# Wilssen_core_v0_201a.net
KiCad netlist of a schematic drawn in EAGLE
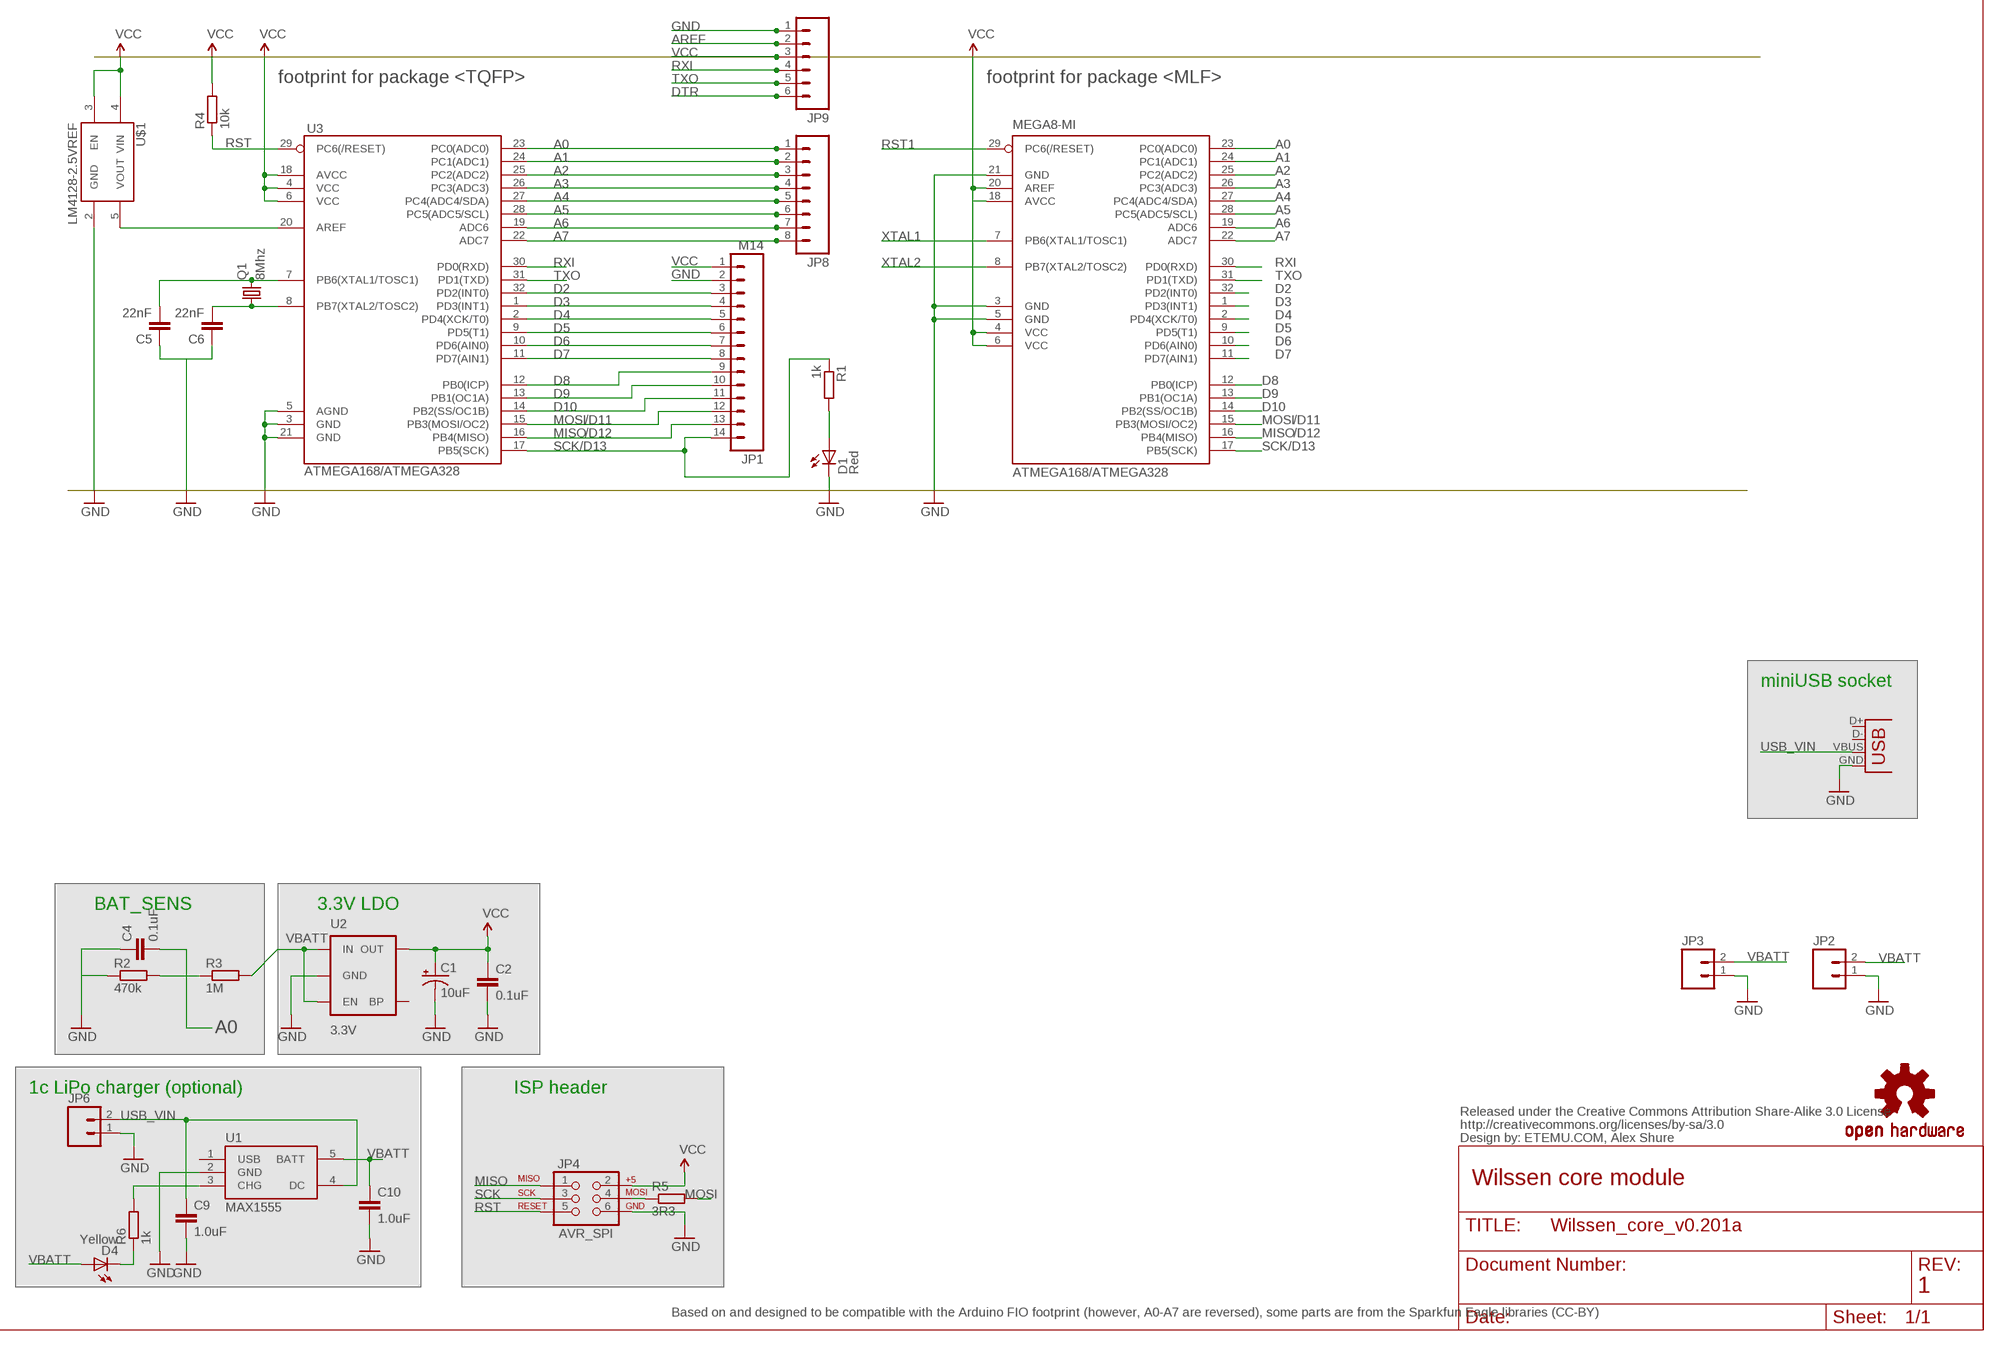
[diagram p0: schematic, sheet 1, part 1 of 2]
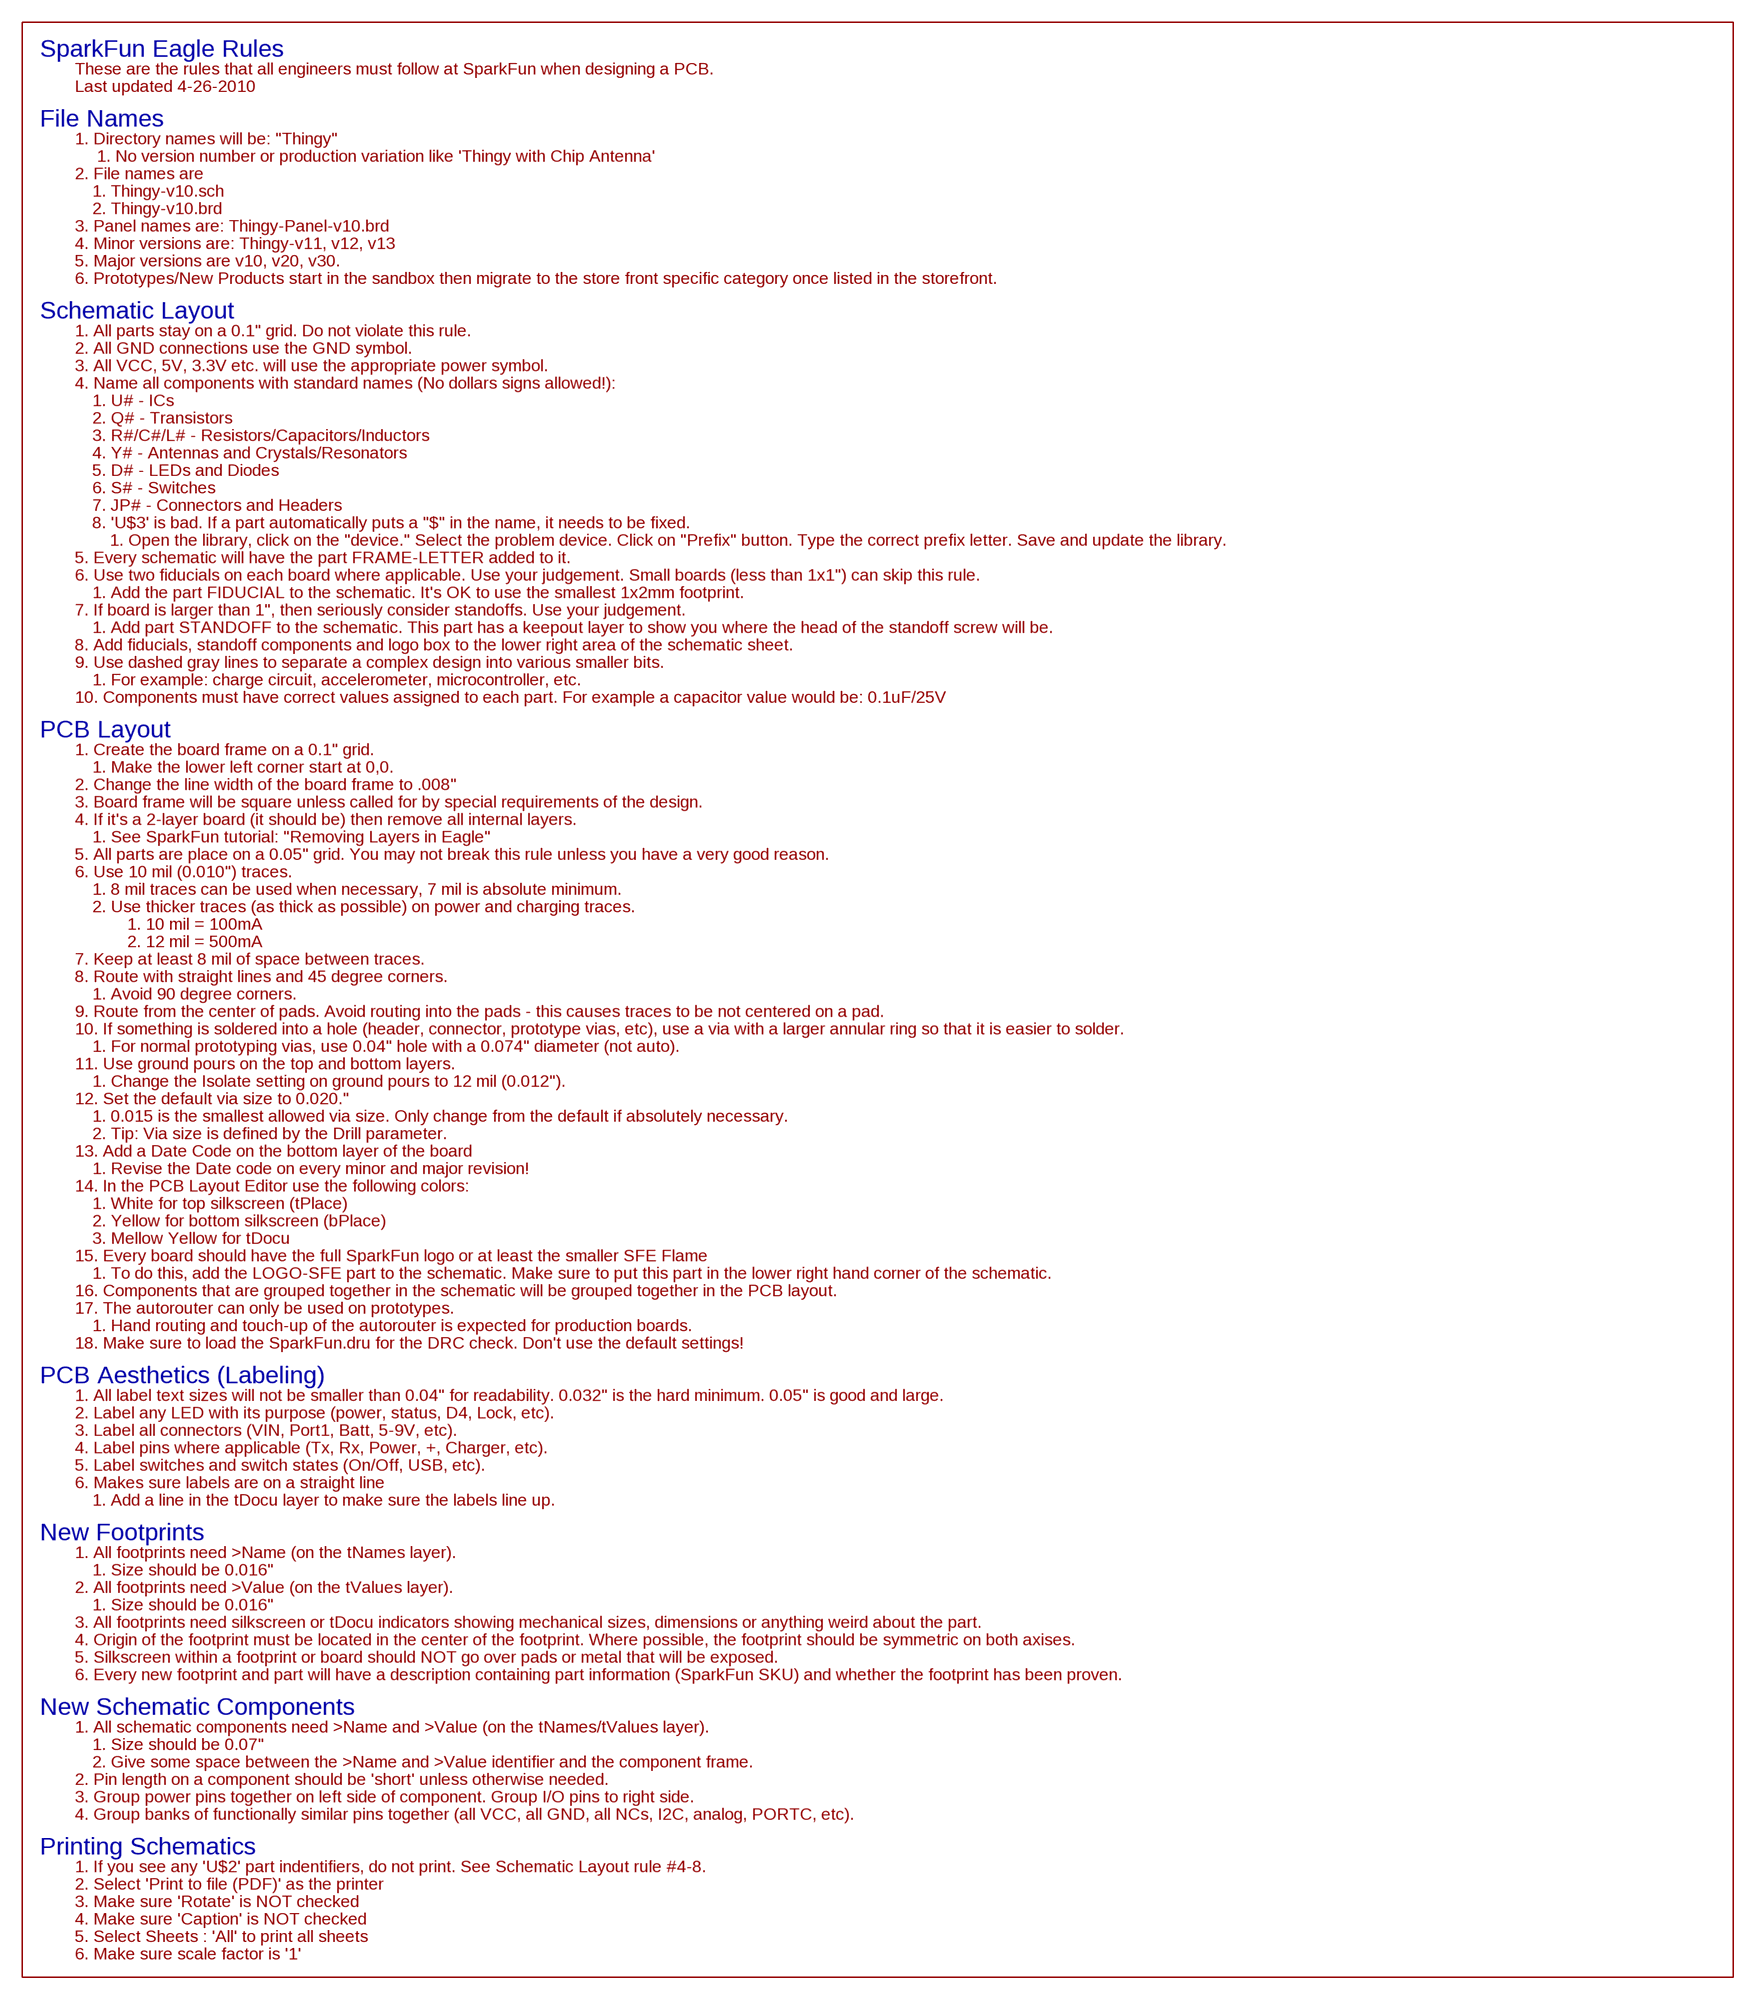
[diagram p1: schematic, sheet 1, part 2 of 2]

(export (version "E")
  (design (tool "Eeschema 10.0.6"))
  (components
    (comp (ref "ATMEGA168/ATMEGA328")
      (value "MEGA8-MI")
      (footprint "eagle-import:MLF32")
      (fields (field (name "MPN") "ATMEGA88PA-MU"))
      (libsource (lib "eagle-import") (part "MEGA8-MI"))
    )
    (comp (ref "C1")
      (value "10uF")
      (footprint "eagle-import:EIA3216")
      (libsource (lib "eagle-import") (part "CAP_POL1206"))
    )
    (comp (ref "C2")
      (value "0.1uF")
      (footprint "eagle-import:0805")
      (libsource (lib "eagle-import") (part "CAP0805"))
    )
    (comp (ref "C4")
      (value "0.1uF")
      (footprint "eagle-import:0805")
      (libsource (lib "eagle-import") (part "CAP0805"))
    )
    (comp (ref "C5")
      (value "22nF")
      (footprint "eagle-import:0805")
      (libsource (lib "eagle-import") (part "CAP0805"))
    )
    (comp (ref "C6")
      (value "22nF")
      (footprint "eagle-import:0805")
      (libsource (lib "eagle-import") (part "CAP0805"))
    )
    (comp (ref "C9")
      (value "1.0uF")
      (footprint "eagle-import:0805")
      (libsource (lib "eagle-import") (part "CAP0805"))
    )
    (comp (ref "C10")
      (value "1.0uF")
      (footprint "eagle-import:0805")
      (libsource (lib "eagle-import") (part "CAP0805"))
    )
    (comp (ref "CC_TEXT1")
      (value "CREATIVE_COMMONS")
      (footprint "eagle-import:CREATIVE_COMMONS")
      (libsource (lib "eagle-import") (part "CREATIVE_COMMONS"))
    )
    (comp (ref "D1")
      (value "Red")
      (footprint "eagle-import:LED-0603")
      (libsource (lib "eagle-import") (part "LED0603"))
    )
    (comp (ref "D4")
      (value "Yellow")
      (footprint "eagle-import:LED-0603")
      (libsource (lib "eagle-import") (part "LED0603"))
    )
    (comp (ref "JP1")
      (value "M14")
      (footprint "eagle-import:1X14")
      (libsource (lib "eagle-import") (part "M14"))
    )
    (comp (ref "JP2")
      (value "M02PTH")
      (footprint "eagle-import:1X02")
      (libsource (lib "eagle-import") (part "M02PTH"))
    )
    (comp (ref "JP3")
      (value "M02-JST-2MM-SMT")
      (footprint "eagle-import:S2B-PH")
      (libsource (lib "eagle-import") (part "M02-JST-2MM-SMT"))
    )
    (comp (ref "JP4")
      (value "AVR_SPI")
      (footprint "eagle-import:2X3")
      (libsource (lib "eagle-import") (part "AVR_SPI_PRG_6PTH"))
    )
    (comp (ref "JP6")
      (value "M02PTH")
      (footprint "eagle-import:1X02")
      (libsource (lib "eagle-import") (part "M02PTH"))
    )
    (comp (ref "JP8")
      (value "M081X08")
      (footprint "eagle-import:1X08")
      (libsource (lib "eagle-import") (part "M081X08"))
    )
    (comp (ref "JP9")
      (value "M06SIP")
      (footprint "eagle-import:1X06")
      (libsource (lib "eagle-import") (part "M06SIP"))
    )
    (comp (ref "LOGO1")
      (value "OSHW-LOGOS")
      (footprint "eagle-import:OSHW-LOGO-S")
      (libsource (lib "eagle-import") (part "OSHW-LOGOS"))
    )
    (comp (ref "Q1")
      (value "8Mhz")
      (footprint "eagle-import:SM49")
      (libsource (lib "eagle-import") (part "CRYSTALSM49"))
    )
    (comp (ref "R1")
      (value "1k")
      (footprint "eagle-import:R0805")
      (libsource (lib "eagle-import") (part "R-EU_R0805"))
    )
    (comp (ref "R2")
      (value "470k")
      (footprint "eagle-import:R0805")
      (libsource (lib "eagle-import") (part "R-EU_R0805"))
    )
    (comp (ref "R3")
      (value "1M")
      (footprint "eagle-import:R0805")
      (libsource (lib "eagle-import") (part "R-EU_R0805"))
    )
    (comp (ref "R4")
      (value "10k")
      (footprint "eagle-import:R0805")
      (libsource (lib "eagle-import") (part "R-EU_R0805"))
    )
    (comp (ref "R5")
      (value "3R3")
      (footprint "eagle-import:R1206")
      (libsource (lib "eagle-import") (part "R-EU_R1206"))
    )
    (comp (ref "R6")
      (value "1k")
      (footprint "eagle-import:R0805")
      (libsource (lib "eagle-import") (part "R-EU_R0805"))
    )
    (comp (ref "U$1")
      (value "LM4128-2.5VREF")
      (footprint "eagle-import:SOT23-5")
      (libsource (lib "eagle-import") (part "LM4128-2.5VREF"))
    )
    (comp (ref "U1")
      (value "MAX1555")
      (footprint "eagle-import:SOT23-5")
      (libsource (lib "eagle-import") (part "MAX1555"))
    )
    (comp (ref "U2")
      (value "3.3V")
      (footprint "eagle-import:SOT23-5")
      (libsource (lib "eagle-import") (part "V_REG_LDOSMD"))
    )
    (comp (ref "U3")
      (value "ATMEGA168/ATMEGA328")
      (footprint "eagle-import:TQFP32-08")
      (libsource (lib "eagle-import") (part "ATMEGA168"))
    )
    (comp (ref "X1")
      (value "USBSMD")
      (footprint "eagle-import:USB-MINIB")
      (libsource (lib "eagle-import") (part "USBSMD"))
    )
  )
  (nets
    (net (code "1") (name "/A0") (class "Default")
      (node (ref "ATMEGA168/ATMEGA328") (pin "23") (pinfunction "PC0(ADC0)_23") (pintype "bidirectional"))
      (node (ref "C4") (pin "2") (pinfunction "2_2") (pintype "passive"))
      (node (ref "JP8") (pin "1") (pinfunction "1_1") (pintype "passive"))
      (node (ref "R2") (pin "2") (pinfunction "2_2") (pintype "passive"))
      (node (ref "R3") (pin "1") (pinfunction "1_1") (pintype "passive"))
      (node (ref "U3") (pin "23") (pinfunction "PC0(ADC0)_23") (pintype "bidirectional"))
    )
    (net (code "2") (name "/A1") (class "Default")
      (node (ref "ATMEGA168/ATMEGA328") (pin "24") (pinfunction "PC1(ADC1)_24") (pintype "bidirectional"))
      (node (ref "JP8") (pin "2") (pinfunction "2_2") (pintype "passive"))
      (node (ref "U3") (pin "24") (pinfunction "PC1(ADC1)_24") (pintype "bidirectional"))
    )
    (net (code "3") (name "/A2") (class "Default")
      (node (ref "ATMEGA168/ATMEGA328") (pin "25") (pinfunction "PC2(ADC2)_25") (pintype "bidirectional"))
      (node (ref "JP8") (pin "3") (pinfunction "3_3") (pintype "passive"))
      (node (ref "U3") (pin "25") (pinfunction "PC2(ADC2)_25") (pintype "bidirectional"))
    )
    (net (code "4") (name "/A3") (class "Default")
      (node (ref "ATMEGA168/ATMEGA328") (pin "26") (pinfunction "PC3(ADC3)_26") (pintype "bidirectional"))
      (node (ref "JP8") (pin "4") (pinfunction "4_4") (pintype "passive"))
      (node (ref "U3") (pin "26") (pinfunction "PC3(ADC3)_26") (pintype "bidirectional"))
    )
    (net (code "5") (name "/A4") (class "Default")
      (node (ref "ATMEGA168/ATMEGA328") (pin "27") (pinfunction "PC4(ADC4/SDA)_27") (pintype "bidirectional"))
      (node (ref "JP8") (pin "5") (pinfunction "5_5") (pintype "passive"))
      (node (ref "U3") (pin "27") (pinfunction "PC4(ADC4/SDA)_27") (pintype "bidirectional"))
    )
    (net (code "6") (name "/A5") (class "Default")
      (node (ref "ATMEGA168/ATMEGA328") (pin "28") (pinfunction "PC5(ADC5/SCL)_28") (pintype "bidirectional"))
      (node (ref "JP8") (pin "6") (pinfunction "6_6") (pintype "passive"))
      (node (ref "U3") (pin "28") (pinfunction "PC5(ADC5/SCL)_28") (pintype "bidirectional"))
    )
    (net (code "7") (name "/A6") (class "Default")
      (node (ref "ATMEGA168/ATMEGA328") (pin "19") (pinfunction "ADC6_19") (pintype "bidirectional"))
      (node (ref "JP8") (pin "7") (pinfunction "7_7") (pintype "passive"))
      (node (ref "U3") (pin "19") (pinfunction "ADC6_19") (pintype "bidirectional"))
    )
    (net (code "8") (name "/A7") (class "Default")
      (node (ref "ATMEGA168/ATMEGA328") (pin "22") (pinfunction "ADC7_22") (pintype "bidirectional"))
      (node (ref "JP8") (pin "8") (pinfunction "8_8") (pintype "passive"))
      (node (ref "U3") (pin "22") (pinfunction "ADC7_22") (pintype "bidirectional"))
    )
    (net (code "9") (name "/AREF") (class "Default")
      (node (ref "JP9") (pin "2") (pinfunction "2_2") (pintype "passive"))
    )
    (net (code "10") (name "/D2") (class "Default")
      (node (ref "ATMEGA168/ATMEGA328") (pin "32") (pinfunction "PD2(INT0)_32") (pintype "bidirectional"))
      (node (ref "JP1") (pin "3") (pinfunction "3_3") (pintype "passive"))
      (node (ref "U3") (pin "32") (pinfunction "PD2(INT0)_32") (pintype "bidirectional"))
    )
    (net (code "11") (name "/D3") (class "Default")
      (node (ref "ATMEGA168/ATMEGA328") (pin "1") (pinfunction "PD3(INT1)_1") (pintype "bidirectional"))
      (node (ref "JP1") (pin "4") (pinfunction "4_4") (pintype "passive"))
      (node (ref "U3") (pin "1") (pinfunction "PD3(INT1)_1") (pintype "bidirectional"))
    )
    (net (code "12") (name "/D4") (class "Default")
      (node (ref "ATMEGA168/ATMEGA328") (pin "2") (pinfunction "PD4(XCK/T0)_2") (pintype "bidirectional"))
      (node (ref "JP1") (pin "5") (pinfunction "5_5") (pintype "passive"))
      (node (ref "U3") (pin "2") (pinfunction "PD4(XCK/T0)_2") (pintype "bidirectional"))
    )
    (net (code "13") (name "/D5") (class "Default")
      (node (ref "ATMEGA168/ATMEGA328") (pin "9") (pinfunction "PD5(T1)_9") (pintype "bidirectional"))
      (node (ref "JP1") (pin "6") (pinfunction "6_6") (pintype "passive"))
      (node (ref "U3") (pin "9") (pinfunction "PD5(T1)_9") (pintype "bidirectional"))
    )
    (net (code "14") (name "/D6") (class "Default")
      (node (ref "ATMEGA168/ATMEGA328") (pin "10") (pinfunction "PD6(AIN0)_10") (pintype "bidirectional"))
      (node (ref "JP1") (pin "7") (pinfunction "7_7") (pintype "passive"))
      (node (ref "U3") (pin "10") (pinfunction "PD6(AIN0)_10") (pintype "bidirectional"))
    )
    (net (code "15") (name "/D7") (class "Default")
      (node (ref "ATMEGA168/ATMEGA328") (pin "11") (pinfunction "PD7(AIN1)_11") (pintype "bidirectional"))
      (node (ref "JP1") (pin "8") (pinfunction "8_8") (pintype "passive"))
      (node (ref "U3") (pin "11") (pinfunction "PD7(AIN1)_11") (pintype "bidirectional"))
    )
    (net (code "16") (name "/D8") (class "Default")
      (node (ref "ATMEGA168/ATMEGA328") (pin "12") (pinfunction "PB0(ICP)_12") (pintype "bidirectional"))
      (node (ref "JP1") (pin "9") (pinfunction "9_9") (pintype "passive"))
      (node (ref "U3") (pin "12") (pinfunction "PB0(ICP)_12") (pintype "bidirectional"))
    )
    (net (code "17") (name "/D9") (class "Default")
      (node (ref "ATMEGA168/ATMEGA328") (pin "13") (pinfunction "PB1(OC1A)_13") (pintype "bidirectional"))
      (node (ref "JP1") (pin "10") (pinfunction "10_10") (pintype "passive"))
      (node (ref "U3") (pin "13") (pinfunction "PB1(OC1A)_13") (pintype "bidirectional"))
    )
    (net (code "18") (name "/D10") (class "Default")
      (node (ref "ATMEGA168/ATMEGA328") (pin "14") (pinfunction "PB2(SS/OC1B)_14") (pintype "bidirectional"))
      (node (ref "JP1") (pin "11") (pinfunction "11_11") (pintype "passive"))
      (node (ref "U3") (pin "14") (pinfunction "PB2(SS/OC1B)_14") (pintype "bidirectional"))
    )
    (net (code "19") (name "/DTR") (class "Default")
      (node (ref "JP9") (pin "6") (pinfunction "6_6") (pintype "passive"))
    )
    (net (code "20") (name "/MISO") (class "Default")
      (node (ref "ATMEGA168/ATMEGA328") (pin "16") (pinfunction "PB4(MISO)_16") (pintype "bidirectional"))
      (node (ref "JP1") (pin "13") (pinfunction "13_13") (pintype "passive"))
      (node (ref "JP4") (pin "1") (pinfunction "1_1") (pintype "passive"))
      (node (ref "U3") (pin "16") (pinfunction "PB4(MISO)_16") (pintype "bidirectional"))
    )
    (net (code "21") (name "/MOSI") (class "Default")
      (node (ref "ATMEGA168/ATMEGA328") (pin "15") (pinfunction "PB3(MOSI/OC2)_15") (pintype "bidirectional"))
      (node (ref "JP1") (pin "12") (pinfunction "12_12") (pintype "passive"))
      (node (ref "R5") (pin "2") (pinfunction "2_2") (pintype "passive"))
      (node (ref "U3") (pin "15") (pinfunction "PB3(MOSI/OC2)_15") (pintype "bidirectional"))
    )
    (net (code "22") (name "/RST") (class "Default")
      (node (ref "JP4") (pin "5") (pinfunction "5_5") (pintype "passive"))
      (node (ref "R4") (pin "1") (pinfunction "1_1") (pintype "passive"))
      (node (ref "U3") (pin "29") (pinfunction "PC6(/RESET)_29") (pintype "bidirectional"))
    )
    (net (code "23") (name "/RST1") (class "Default")
      (node (ref "ATMEGA168/ATMEGA328") (pin "29") (pinfunction "PC6(/RESET)_29") (pintype "bidirectional"))
    )
    (net (code "24") (name "/RXI") (class "Default")
      (node (ref "ATMEGA168/ATMEGA328") (pin "30") (pinfunction "PD0(RXD)_30") (pintype "bidirectional"))
      (node (ref "JP9") (pin "4") (pinfunction "4_4") (pintype "passive"))
      (node (ref "U3") (pin "30") (pinfunction "PD0(RXD)_30") (pintype "bidirectional"))
    )
    (net (code "25") (name "/SCK") (class "Default")
      (node (ref "ATMEGA168/ATMEGA328") (pin "17") (pinfunction "PB5(SCK)_17") (pintype "bidirectional"))
      (node (ref "JP1") (pin "14") (pinfunction "14_14") (pintype "passive"))
      (node (ref "JP4") (pin "3") (pinfunction "3_3") (pintype "passive"))
      (node (ref "R1") (pin "1") (pinfunction "1_1") (pintype "passive"))
      (node (ref "U3") (pin "17") (pinfunction "PB5(SCK)_17") (pintype "bidirectional"))
    )
    (net (code "26") (name "/TXO") (class "Default")
      (node (ref "ATMEGA168/ATMEGA328") (pin "31") (pinfunction "PD1(TXD)_31") (pintype "bidirectional"))
      (node (ref "JP9") (pin "5") (pinfunction "5_5") (pintype "passive"))
      (node (ref "U3") (pin "31") (pinfunction "PD1(TXD)_31") (pintype "bidirectional"))
    )
    (net (code "27") (name "/USB_VIN") (class "Default")
      (node (ref "C9") (pin "1") (pinfunction "1_1") (pintype "passive"))
      (node (ref "JP6") (pin "2") (pinfunction "2_2") (pintype "passive"))
      (node (ref "U1") (pin "4") (pinfunction "DC_4") (pintype "bidirectional"))
      (node (ref "X1") (pin "VBUS") (pinfunction "VBUS_VBUS") (pintype "bidirectional"))
    )
    (net (code "28") (name "/VBATT") (class "Default")
      (node (ref "C10") (pin "1") (pinfunction "1_1") (pintype "passive"))
      (node (ref "D4") (pin "A") (pinfunction "A_A") (pintype "passive"))
      (node (ref "JP2") (pin "2") (pinfunction "2_2") (pintype "passive"))
      (node (ref "JP3") (pin "2") (pinfunction "2_2") (pintype "passive"))
      (node (ref "R3") (pin "2") (pinfunction "2_2") (pintype "passive"))
      (node (ref "U1") (pin "5") (pinfunction "BATT_5") (pintype "bidirectional"))
      (node (ref "U2") (pin "1") (pinfunction "IN_1") (pintype "input"))
      (node (ref "U2") (pin "3") (pinfunction "EN_3") (pintype "input"))
    )
    (net (code "29") (name "/XTAL1") (class "Default")
      (node (ref "ATMEGA168/ATMEGA328") (pin "7") (pinfunction "PB6(XTAL1/TOSC1)_7") (pintype "bidirectional"))
      (node (ref "C5") (pin "2") (pinfunction "2_2") (pintype "passive"))
      (node (ref "Q1") (pin "2") (pinfunction "2_2") (pintype "passive"))
      (node (ref "U3") (pin "7") (pinfunction "PB6(XTAL1/TOSC1)_7") (pintype "bidirectional"))
    )
    (net (code "30") (name "/XTAL2") (class "Default")
      (node (ref "ATMEGA168/ATMEGA328") (pin "8") (pinfunction "PB7(XTAL2/TOSC2)_8") (pintype "bidirectional"))
      (node (ref "C6") (pin "2") (pinfunction "2_2") (pintype "passive"))
      (node (ref "Q1") (pin "1") (pinfunction "1_1") (pintype "passive"))
      (node (ref "U3") (pin "8") (pinfunction "PB7(XTAL2/TOSC2)_8") (pintype "bidirectional"))
    )
    (net (code "31") (name "GND") (class "Default")
      (node (ref "ATMEGA168/ATMEGA328") (pin "21") (pinfunction "GND_21") (pintype "power_in"))
      (node (ref "ATMEGA168/ATMEGA328") (pin "3") (pinfunction "GND_3") (pintype "power_in"))
      (node (ref "ATMEGA168/ATMEGA328") (pin "5") (pinfunction "GND_5") (pintype "power_in"))
      (node (ref "C1") (pin "C") (pinfunction "-_C") (pintype "passive"))
      (node (ref "C10") (pin "2") (pinfunction "2_2") (pintype "passive"))
      (node (ref "C2") (pin "2") (pinfunction "2_2") (pintype "passive"))
      (node (ref "C4") (pin "1") (pinfunction "1_1") (pintype "passive"))
      (node (ref "C5") (pin "1") (pinfunction "1_1") (pintype "passive"))
      (node (ref "C6") (pin "1") (pinfunction "1_1") (pintype "passive"))
      (node (ref "C9") (pin "2") (pinfunction "2_2") (pintype "passive"))
      (node (ref "D1") (pin "C") (pinfunction "C_C") (pintype "passive"))
      (node (ref "JP1") (pin "2") (pinfunction "2_2") (pintype "passive"))
      (node (ref "JP2") (pin "1") (pinfunction "1_1") (pintype "passive"))
      (node (ref "JP3") (pin "1") (pinfunction "1_1") (pintype "passive"))
      (node (ref "JP4") (pin "6") (pinfunction "6_6") (pintype "passive"))
      (node (ref "JP6") (pin "1") (pinfunction "1_1") (pintype "passive"))
      (node (ref "JP9") (pin "1") (pinfunction "1_1") (pintype "passive"))
      (node (ref "R2") (pin "1") (pinfunction "1_1") (pintype "passive"))
      (node (ref "U$1") (pin "2") (pinfunction "GND_2") (pintype "bidirectional"))
      (node (ref "U1") (pin "2") (pinfunction "GND_2") (pintype "bidirectional"))
      (node (ref "U2") (pin "2") (pinfunction "GND_2") (pintype "input"))
      (node (ref "U3") (pin "21") (pinfunction "GND_21") (pintype "bidirectional"))
      (node (ref "U3") (pin "3") (pinfunction "GND_3") (pintype "bidirectional"))
      (node (ref "U3") (pin "5") (pinfunction "AGND_5") (pintype "bidirectional"))
      (node (ref "X1") (pin "GND") (pinfunction "GND_GND") (pintype "bidirectional"))
    )
    (net (code "32") (name "Net-(D1-PadA)") (class "Default")
      (node (ref "D1") (pin "A") (pinfunction "A_A") (pintype "passive"))
      (node (ref "R1") (pin "2") (pinfunction "2_2") (pintype "passive"))
    )
    (net (code "33") (name "Net-(D4-PadC)") (class "Default")
      (node (ref "D4") (pin "C") (pinfunction "C_C") (pintype "passive"))
      (node (ref "R6") (pin "1") (pinfunction "1_1") (pintype "passive"))
    )
    (net (code "34") (name "Net-(JP4-Pad4)") (class "Default")
      (node (ref "JP4") (pin "4") (pinfunction "4_4") (pintype "passive"))
      (node (ref "R5") (pin "1") (pinfunction "1_1") (pintype "passive"))
    )
    (net (code "35") (name "Net-(U$1-VOUT)") (class "Default")
      (node (ref "U$1") (pin "5") (pinfunction "VOUT_5") (pintype "bidirectional"))
      (node (ref "U3") (pin "20") (pinfunction "AREF_20") (pintype "bidirectional"))
    )
    (net (code "36") (name "Net-(U1-CHG)") (class "Default")
      (node (ref "R6") (pin "2") (pinfunction "2_2") (pintype "passive"))
      (node (ref "U1") (pin "3") (pinfunction "CHG_3") (pintype "bidirectional"))
    )
    (net (code "37") (name "VCC") (class "Default")
      (node (ref "ATMEGA168/ATMEGA328") (pin "18") (pinfunction "AVCC_18") (pintype "power_in"))
      (node (ref "ATMEGA168/ATMEGA328") (pin "20") (pinfunction "AREF_20") (pintype "passive"))
      (node (ref "ATMEGA168/ATMEGA328") (pin "4") (pinfunction "VCC_4") (pintype "power_in"))
      (node (ref "ATMEGA168/ATMEGA328") (pin "6") (pinfunction "VCC_6") (pintype "power_in"))
      (node (ref "C1") (pin "A") (pinfunction "+_A") (pintype "passive"))
      (node (ref "C2") (pin "1") (pinfunction "1_1") (pintype "passive"))
      (node (ref "JP1") (pin "1") (pinfunction "1_1") (pintype "passive"))
      (node (ref "JP4") (pin "2") (pinfunction "2_2") (pintype "passive"))
      (node (ref "JP9") (pin "3") (pinfunction "3_3") (pintype "passive"))
      (node (ref "R4") (pin "2") (pinfunction "2_2") (pintype "passive"))
      (node (ref "U$1") (pin "3") (pinfunction "EN_3") (pintype "bidirectional"))
      (node (ref "U$1") (pin "4") (pinfunction "VIN_4") (pintype "bidirectional"))
      (node (ref "U2") (pin "5") (pinfunction "OUT_5") (pintype "passive"))
      (node (ref "U3") (pin "18") (pinfunction "AVCC_18") (pintype "bidirectional"))
      (node (ref "U3") (pin "4") (pinfunction "VCC_4") (pintype "bidirectional"))
      (node (ref "U3") (pin "6") (pinfunction "VCC_6") (pintype "bidirectional"))
    )
    (net (code "38") (name "unconnected-(U1-USB-Pad1)") (class "Default")
      (node (ref "U1") (pin "1") (pinfunction "USB_1") (pintype "bidirectional"))
    )
    (net (code "39") (name "unconnected-(U2-BP-Pad4)") (class "Default")
      (node (ref "U2") (pin "4") (pinfunction "BP_4") (pintype "input"))
    )
    (net (code "40") (name "unconnected-(X1-PadD+)") (class "Default")
      (node (ref "X1") (pin "D+") (pinfunction "D+_D+") (pintype "bidirectional"))
    )
    (net (code "41") (name "unconnected-(X1-PadD-)") (class "Default")
      (node (ref "X1") (pin "D-") (pinfunction "D-_D-") (pintype "bidirectional"))
    )
  )
)
